# Laser_Breakout.net
KiCad netlist of a schematic drawn in EAGLE
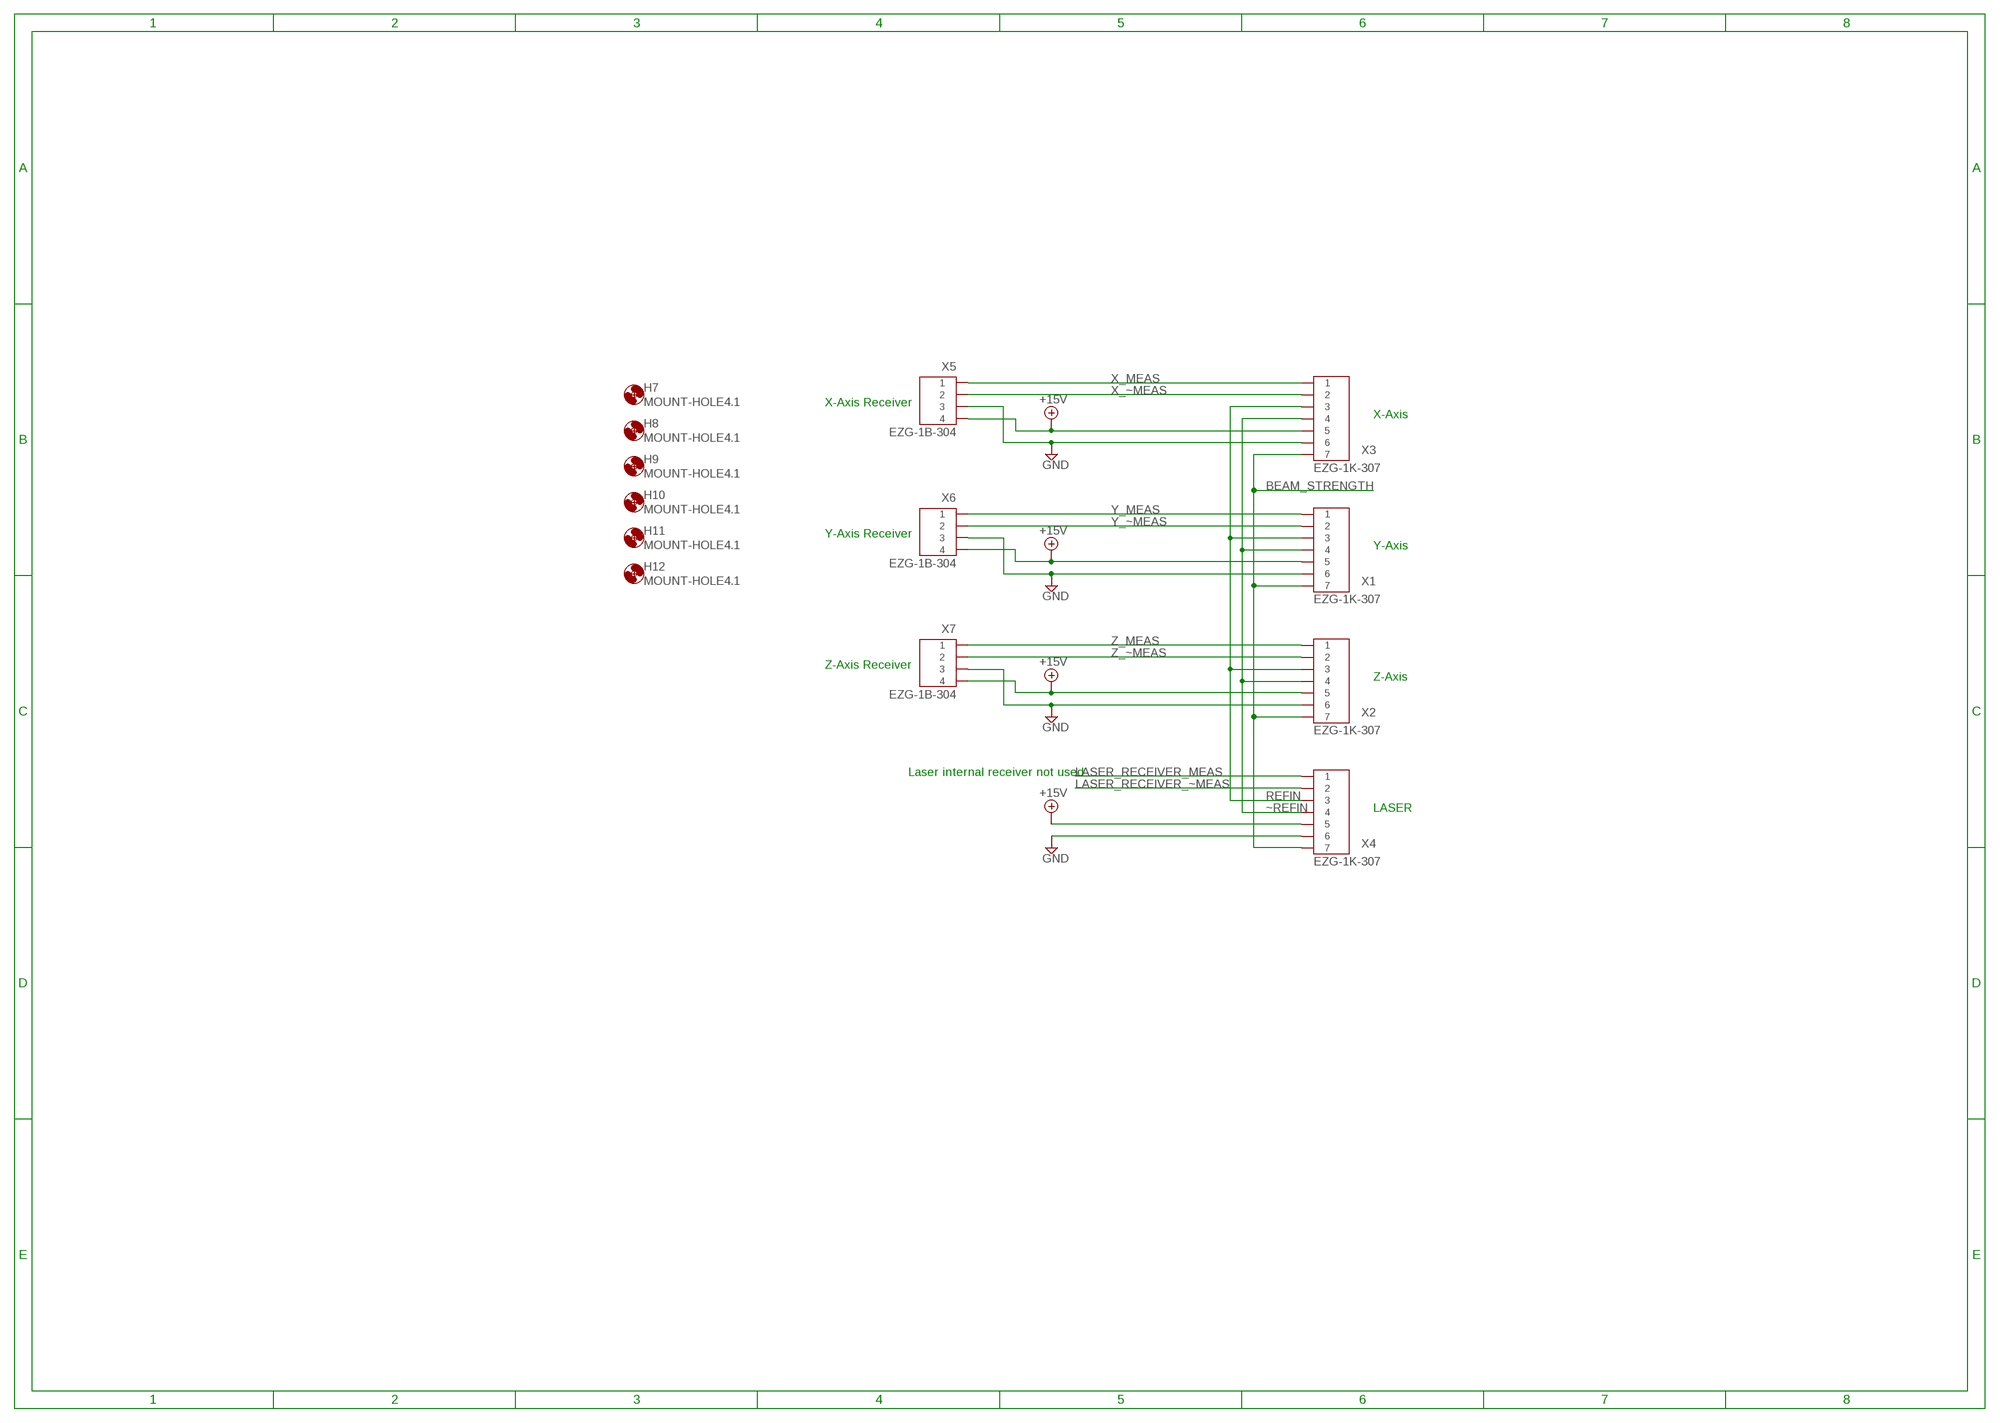
[diagram p0: schematic, sheet 1]

(export (version "E")
  (design (tool "Eeschema 10.0.6"))
  (components
    (comp (ref "H7")
      (value "MOUNT-HOLE4.1")
      (footprint "eagle-import:4,1")
      (libsource (lib "eagle-import") (part "MOUNT-HOLE4.1"))
    )
    (comp (ref "H8")
      (value "MOUNT-HOLE4.1")
      (footprint "eagle-import:4,1")
      (libsource (lib "eagle-import") (part "MOUNT-HOLE4.1"))
    )
    (comp (ref "H9")
      (value "MOUNT-HOLE4.1")
      (footprint "eagle-import:4,1")
      (libsource (lib "eagle-import") (part "MOUNT-HOLE4.1"))
    )
    (comp (ref "H10")
      (value "MOUNT-HOLE4.1")
      (footprint "eagle-import:4,1")
      (libsource (lib "eagle-import") (part "MOUNT-HOLE4.1"))
    )
    (comp (ref "H11")
      (value "MOUNT-HOLE4.1")
      (footprint "eagle-import:4,1")
      (libsource (lib "eagle-import") (part "MOUNT-HOLE4.1"))
    )
    (comp (ref "H12")
      (value "MOUNT-HOLE4.1")
      (footprint "eagle-import:4,1")
      (libsource (lib "eagle-import") (part "MOUNT-HOLE4.1"))
    )
    (comp (ref "X1")
      (value "EZG-1K-307")
      (footprint "eagle-import:EZG-1B-1K-307")
      (libsource (lib "eagle-import") (part "EZG-?-3071K"))
    )
    (comp (ref "X2")
      (value "EZG-1K-307")
      (footprint "eagle-import:EZG-1B-1K-307")
      (libsource (lib "eagle-import") (part "EZG-?-3071K"))
    )
    (comp (ref "X3")
      (value "EZG-1K-307")
      (footprint "eagle-import:EZG-1B-1K-307")
      (libsource (lib "eagle-import") (part "EZG-?-3071K"))
    )
    (comp (ref "X4")
      (value "EZG-1K-307")
      (footprint "eagle-import:EZG-1B-1K-307")
      (libsource (lib "eagle-import") (part "EZG-?-3071K"))
    )
    (comp (ref "X5")
      (value "EZG-1B-304")
      (footprint "eagle-import:EZG-1B-1K-304")
      (libsource (lib "eagle-import") (part "EZG-?-3041B"))
    )
    (comp (ref "X6")
      (value "EZG-1B-304")
      (footprint "eagle-import:EZG-1B-1K-304")
      (libsource (lib "eagle-import") (part "EZG-?-3041B"))
    )
    (comp (ref "X7")
      (value "EZG-1B-304")
      (footprint "eagle-import:EZG-1B-1K-304")
      (libsource (lib "eagle-import") (part "EZG-?-3041B"))
    )
  )
  (nets
    (net (code "1") (name "+15V") (class "Default")
      (node (ref "X1") (pin "5") (pinfunction "5_5") (pintype "passive"))
      (node (ref "X2") (pin "5") (pinfunction "5_5") (pintype "passive"))
      (node (ref "X3") (pin "5") (pinfunction "5_5") (pintype "passive"))
      (node (ref "X4") (pin "5") (pinfunction "5_5") (pintype "passive"))
      (node (ref "X5") (pin "4") (pinfunction "4_4") (pintype "passive"))
      (node (ref "X6") (pin "4") (pinfunction "4_4") (pintype "passive"))
      (node (ref "X7") (pin "4") (pinfunction "4_4") (pintype "passive"))
    )
    (net (code "2") (name "/BEAM_STRENGTH") (class "Default")
      (node (ref "X1") (pin "7") (pinfunction "7_7") (pintype "passive"))
      (node (ref "X2") (pin "7") (pinfunction "7_7") (pintype "passive"))
      (node (ref "X3") (pin "7") (pinfunction "7_7") (pintype "passive"))
      (node (ref "X4") (pin "7") (pinfunction "7_7") (pintype "passive"))
    )
    (net (code "3") (name "/LASER_RECEIVER_MEAS") (class "Default")
      (node (ref "X4") (pin "1") (pinfunction "1_1") (pintype "passive"))
    )
    (net (code "4") (name "/LASER_RECEIVER_~{MEAS}") (class "Default")
      (node (ref "X4") (pin "2") (pinfunction "2_2") (pintype "passive"))
    )
    (net (code "5") (name "/REFIN") (class "Default")
      (node (ref "X1") (pin "3") (pinfunction "3_3") (pintype "passive"))
      (node (ref "X2") (pin "3") (pinfunction "3_3") (pintype "passive"))
      (node (ref "X3") (pin "3") (pinfunction "3_3") (pintype "passive"))
      (node (ref "X4") (pin "3") (pinfunction "3_3") (pintype "passive"))
    )
    (net (code "6") (name "/X_MEAS") (class "Default")
      (node (ref "X3") (pin "1") (pinfunction "1_1") (pintype "passive"))
      (node (ref "X5") (pin "1") (pinfunction "1_1") (pintype "passive"))
    )
    (net (code "7") (name "/X_~{MEAS}") (class "Default")
      (node (ref "X3") (pin "2") (pinfunction "2_2") (pintype "passive"))
      (node (ref "X5") (pin "2") (pinfunction "2_2") (pintype "passive"))
    )
    (net (code "8") (name "/Y_MEAS") (class "Default")
      (node (ref "X1") (pin "1") (pinfunction "1_1") (pintype "passive"))
      (node (ref "X6") (pin "1") (pinfunction "1_1") (pintype "passive"))
    )
    (net (code "9") (name "/Y_~{MEAS}") (class "Default")
      (node (ref "X1") (pin "2") (pinfunction "2_2") (pintype "passive"))
      (node (ref "X6") (pin "2") (pinfunction "2_2") (pintype "passive"))
    )
    (net (code "10") (name "/Z_MEAS") (class "Default")
      (node (ref "X2") (pin "1") (pinfunction "1_1") (pintype "passive"))
      (node (ref "X7") (pin "1") (pinfunction "1_1") (pintype "passive"))
    )
    (net (code "11") (name "/Z_~{MEAS}") (class "Default")
      (node (ref "X2") (pin "2") (pinfunction "2_2") (pintype "passive"))
      (node (ref "X7") (pin "2") (pinfunction "2_2") (pintype "passive"))
    )
    (net (code "12") (name "/~{REFIN}") (class "Default")
      (node (ref "X1") (pin "4") (pinfunction "4_4") (pintype "passive"))
      (node (ref "X2") (pin "4") (pinfunction "4_4") (pintype "passive"))
      (node (ref "X3") (pin "4") (pinfunction "4_4") (pintype "passive"))
      (node (ref "X4") (pin "4") (pinfunction "4_4") (pintype "passive"))
    )
    (net (code "13") (name "GND") (class "Default")
      (node (ref "X1") (pin "6") (pinfunction "6_6") (pintype "passive"))
      (node (ref "X2") (pin "6") (pinfunction "6_6") (pintype "passive"))
      (node (ref "X3") (pin "6") (pinfunction "6_6") (pintype "passive"))
      (node (ref "X4") (pin "6") (pinfunction "6_6") (pintype "passive"))
      (node (ref "X5") (pin "3") (pinfunction "3_3") (pintype "passive"))
      (node (ref "X6") (pin "3") (pinfunction "3_3") (pintype "passive"))
      (node (ref "X7") (pin "3") (pinfunction "3_3") (pintype "passive"))
    )
  )
)
